# can_rs485.net
KiCad netlist of a schematic drawn in Altium Designer
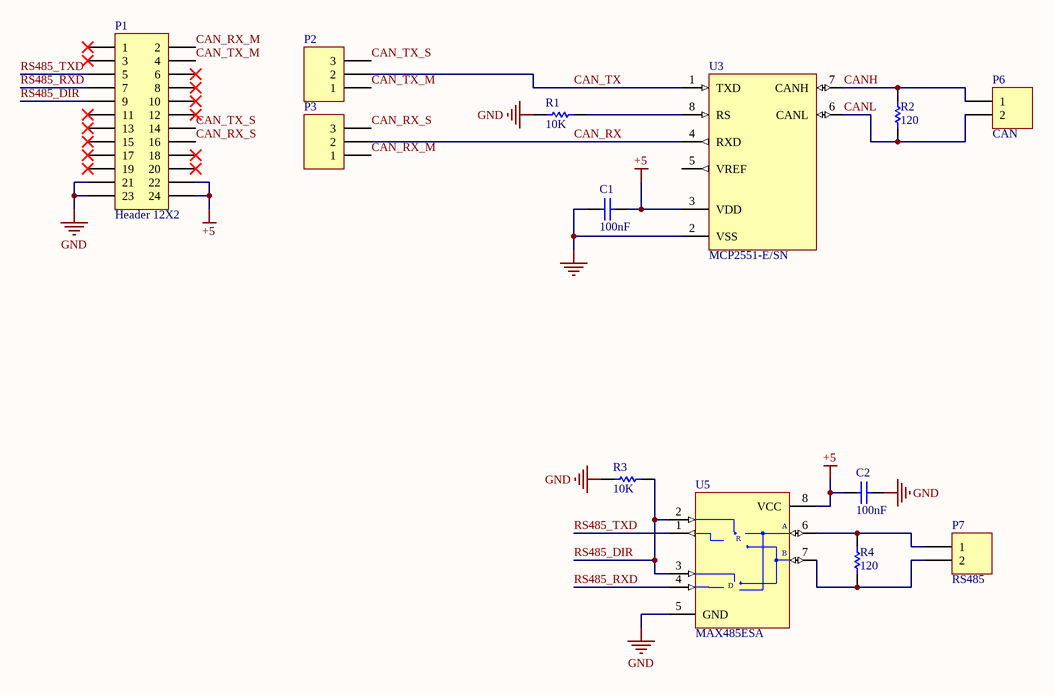
[diagram p0: can&rs485.SchDoc]

(export (version "E")
  (design (tool "Eeschema 10.0.6"))
  (components
    (comp (ref "C1")
      (value "100nF")
      (footprint "CAPC4817X12N")
      (description "Capacitor")
      (fields (field (name "PUBLISHER") "Altium Limited"))
      (libsource (lib "Miscellaneous Devices") (part "CAP"))
    )
    (comp (ref "C2")
      (value "100nF")
      (footprint "CAPC4817X12N")
      (description "Capacitor")
      (fields (field (name "PUBLISHER") "Altium Limited"))
      (libsource (lib "Miscellaneous Devices") (part "CAP"))
    )
    (comp (ref "P1")
      (value "Header 12X2")
      (footprint "HDR2X12")
      (description "Header, 12-Pin, Dual row")
      (fields (field (name "PUBLISHER") "Altium Limited"))
      (libsource (lib "Miscellaneous Connectors") (part "Header 12X2"))
    )
    (comp (ref "P2")
      (value "Header 3")
      (footprint "HDR1X3")
      (description "Header, 3-Pin")
      (fields (field (name "PUBLISHER") "Altium Limited"))
      (libsource (lib "Miscellaneous Connectors") (part "Header 3"))
    )
    (comp (ref "P3")
      (value "Header 3")
      (footprint "HDR1X3")
      (description "Header, 3-Pin")
      (fields (field (name "PUBLISHER") "Altium Limited"))
      (libsource (lib "Miscellaneous Connectors") (part "Header 3"))
    )
    (comp (ref "P6")
      (value "CAN")
      (footprint "POWER")
      (description "Header, 2-Pin")
      (fields (field (name "PUBLISHER") "Altium Limited"))
      (libsource (lib "Miscellaneous Connectors") (part "Header 2"))
    )
    (comp (ref "P7")
      (value "RS485")
      (footprint "POWER")
      (description "Header, 2-Pin")
      (fields (field (name "PUBLISHER") "Altium Limited"))
      (libsource (lib "Miscellaneous Connectors") (part "Header 2"))
    )
    (comp (ref "R1")
      (value "10K")
      (footprint "RESC4817X04N")
      (description "Resistor")
      (fields (field (name "PUBLISHER") "Altium Limited"))
      (libsource (lib "Miscellaneous Devices") (part "res1"))
    )
    (comp (ref "R2")
      (value "120")
      (footprint "RESC4817X04N")
      (description "Resistor")
      (fields (field (name "PUBLISHER") "Altium Limited"))
      (libsource (lib "Miscellaneous Devices") (part "res1"))
    )
    (comp (ref "R3")
      (value "10K")
      (footprint "RESC4817X04N")
      (description "Resistor")
      (fields (field (name "PUBLISHER") "Altium Limited"))
      (libsource (lib "Miscellaneous Devices") (part "res1"))
    )
    (comp (ref "R4")
      (value "120")
      (footprint "RESC4817X04N")
      (description "Resistor")
      (fields (field (name "PUBLISHER") "Altium Limited"))
      (libsource (lib "Miscellaneous Devices") (part "res1"))
    )
    (comp (ref "U3")
      (value "MCP2551-E/SN")
      (footprint "SOIC-SN8_N")
      (description "High-Speed CAN Transceiver, 8-Pin SOIC, Extended Temperature")
      (fields (field (name "MANUFACTURER") "Microchip"))
      (libsource (lib "Microchip Interface") (part "MCP2551-E/SN"))
    )
    (comp (ref "U5")
      (value "MAX485ESA")
      (footprint "NSO8_N")
      (description "Low-Power, Slew-Rate-Limited RS-485/RS-422 Transceiver")
      (fields (field (name "PUBLISHER") "Altium Limited"))
      (libsource (lib "Maxim Communication Transceiver") (part "MAX485ESA"))
    )
  )
  (nets
    (net (code "1") (name "+5") (class "Default")
      (node (ref "C1") (pin "2") (pinfunction "2_2") (pintype "passive"))
      (node (ref "C2") (pin "1") (pinfunction "1_1") (pintype "passive"))
      (node (ref "P1") (pin "22") (pinfunction "22_22") (pintype "passive"))
      (node (ref "P1") (pin "24") (pinfunction "24_24") (pintype "passive"))
      (node (ref "U3") (pin "3") (pinfunction "VDD_3") (pintype "power_in"))
      (node (ref "U5") (pin "8") (pinfunction "VCC_8") (pintype "power_in"))
    )
    (net (code "2") (name "/CANH") (class "Default")
      (node (ref "P6") (pin "1") (pinfunction "1_1") (pintype "passive"))
      (node (ref "R2") (pin "2") (pinfunction "2_2") (pintype "passive"))
      (node (ref "U3") (pin "7") (pinfunction "CANH_7") (pintype "bidirectional"))
    )
    (net (code "3") (name "/CANL") (class "Default")
      (node (ref "P6") (pin "2") (pinfunction "2_2") (pintype "passive"))
      (node (ref "R2") (pin "1") (pinfunction "1_1") (pintype "passive"))
      (node (ref "U3") (pin "6") (pinfunction "CANL_6") (pintype "bidirectional"))
    )
    (net (code "4") (name "/CAN_RX") (class "Default")
      (node (ref "P3") (pin "2") (pinfunction "2_2") (pintype "passive"))
      (node (ref "U3") (pin "4") (pinfunction "RXD_4") (pintype "output"))
    )
    (net (code "5") (name "/CAN_RX_M") (class "Default")
      (node (ref "P1") (pin "2") (pinfunction "2_2") (pintype "passive"))
      (node (ref "P3") (pin "1") (pinfunction "1_1") (pintype "passive"))
    )
    (net (code "6") (name "/CAN_RX_S") (class "Default")
      (node (ref "P1") (pin "16") (pinfunction "16_16") (pintype "passive"))
      (node (ref "P3") (pin "3") (pinfunction "3_3") (pintype "passive"))
    )
    (net (code "7") (name "/CAN_TX") (class "Default")
      (node (ref "P2") (pin "2") (pinfunction "2_2") (pintype "passive"))
      (node (ref "U3") (pin "1") (pinfunction "TXD_1") (pintype "input"))
    )
    (net (code "8") (name "/CAN_TX_M") (class "Default")
      (node (ref "P1") (pin "4") (pinfunction "4_4") (pintype "passive"))
      (node (ref "P2") (pin "1") (pinfunction "1_1") (pintype "passive"))
    )
    (net (code "9") (name "/CAN_TX_S") (class "Default")
      (node (ref "P1") (pin "14") (pinfunction "14_14") (pintype "passive"))
      (node (ref "P2") (pin "3") (pinfunction "3_3") (pintype "passive"))
    )
    (net (code "10") (name "/RS485_DIR") (class "Default")
      (node (ref "P1") (pin "9") (pinfunction "9_9") (pintype "passive"))
      (node (ref "R3") (pin "1") (pinfunction "1_1") (pintype "passive"))
      (node (ref "U5") (pin "2") (pinfunction "~{RE}_2") (pintype "input"))
      (node (ref "U5") (pin "3") (pinfunction "DE_3") (pintype "input"))
    )
    (net (code "11") (name "/RS485_RXD") (class "Default")
      (node (ref "P1") (pin "7") (pinfunction "7_7") (pintype "passive"))
      (node (ref "U5") (pin "4") (pinfunction "DI_4") (pintype "input"))
    )
    (net (code "12") (name "/RS485_TXD") (class "Default")
      (node (ref "P1") (pin "5") (pinfunction "5_5") (pintype "passive"))
      (node (ref "U5") (pin "1") (pinfunction "RO_1") (pintype "output"))
    )
    (net (code "13") (name "GND") (class "Default")
      (node (ref "C1") (pin "1") (pinfunction "1_1") (pintype "passive"))
      (node (ref "C2") (pin "2") (pinfunction "2_2") (pintype "passive"))
      (node (ref "P1") (pin "21") (pinfunction "21_21") (pintype "passive"))
      (node (ref "P1") (pin "23") (pinfunction "23_23") (pintype "passive"))
      (node (ref "R1") (pin "2") (pinfunction "2_2") (pintype "passive"))
      (node (ref "R3") (pin "2") (pinfunction "2_2") (pintype "passive"))
      (node (ref "U3") (pin "2") (pinfunction "VSS_2") (pintype "power_in"))
      (node (ref "U5") (pin "5") (pinfunction "GND_5") (pintype "power_in"))
    )
    (net (code "14") (name "Net-(U3-RS)") (class "Default")
      (node (ref "R1") (pin "1") (pinfunction "1_1") (pintype "passive"))
      (node (ref "U3") (pin "8") (pinfunction "RS_8") (pintype "input"))
    )
    (net (code "15") (name "Net-(U5-A)") (class "Default")
      (node (ref "P7") (pin "1") (pinfunction "1_1") (pintype "passive"))
      (node (ref "R4") (pin "2") (pinfunction "2_2") (pintype "passive"))
      (node (ref "U5") (pin "6") (pinfunction "A_6") (pintype "bidirectional"))
    )
    (net (code "16") (name "Net-(U5-B)") (class "Default")
      (node (ref "P7") (pin "2") (pinfunction "2_2") (pintype "passive"))
      (node (ref "R4") (pin "1") (pinfunction "1_1") (pintype "passive"))
      (node (ref "U5") (pin "7") (pinfunction "B_7") (pintype "bidirectional"))
    )
    (net (code "17") (name "unconnected-(P1-Pad1)") (class "Default")
      (node (ref "P1") (pin "1") (pinfunction "1_1") (pintype "passive+no_connect"))
    )
    (net (code "18") (name "unconnected-(P1-Pad3)") (class "Default")
      (node (ref "P1") (pin "3") (pinfunction "3_3") (pintype "passive+no_connect"))
    )
    (net (code "19") (name "unconnected-(P1-Pad6)") (class "Default")
      (node (ref "P1") (pin "6") (pinfunction "6_6") (pintype "passive+no_connect"))
    )
    (net (code "20") (name "unconnected-(P1-Pad8)") (class "Default")
      (node (ref "P1") (pin "8") (pinfunction "8_8") (pintype "passive+no_connect"))
    )
    (net (code "21") (name "unconnected-(P1-Pad10)") (class "Default")
      (node (ref "P1") (pin "10") (pinfunction "10_10") (pintype "passive+no_connect"))
    )
    (net (code "22") (name "unconnected-(P1-Pad11)") (class "Default")
      (node (ref "P1") (pin "11") (pinfunction "11_11") (pintype "passive+no_connect"))
    )
    (net (code "23") (name "unconnected-(P1-Pad12)") (class "Default")
      (node (ref "P1") (pin "12") (pinfunction "12_12") (pintype "passive+no_connect"))
    )
    (net (code "24") (name "unconnected-(P1-Pad13)") (class "Default")
      (node (ref "P1") (pin "13") (pinfunction "13_13") (pintype "passive+no_connect"))
    )
    (net (code "25") (name "unconnected-(P1-Pad15)") (class "Default")
      (node (ref "P1") (pin "15") (pinfunction "15_15") (pintype "passive+no_connect"))
    )
    (net (code "26") (name "unconnected-(P1-Pad17)") (class "Default")
      (node (ref "P1") (pin "17") (pinfunction "17_17") (pintype "passive+no_connect"))
    )
    (net (code "27") (name "unconnected-(P1-Pad18)") (class "Default")
      (node (ref "P1") (pin "18") (pinfunction "18_18") (pintype "passive+no_connect"))
    )
    (net (code "28") (name "unconnected-(P1-Pad19)") (class "Default")
      (node (ref "P1") (pin "19") (pinfunction "19_19") (pintype "passive+no_connect"))
    )
    (net (code "29") (name "unconnected-(P1-Pad20)") (class "Default")
      (node (ref "P1") (pin "20") (pinfunction "20_20") (pintype "passive+no_connect"))
    )
    (net (code "30") (name "unconnected-(U3-VREF-Pad5)") (class "Default")
      (node (ref "U3") (pin "5") (pinfunction "VREF_5") (pintype "output"))
    )
  )
)
